# hermes_v2.net
KiCad netlist of a schematic drawn in EAGLE
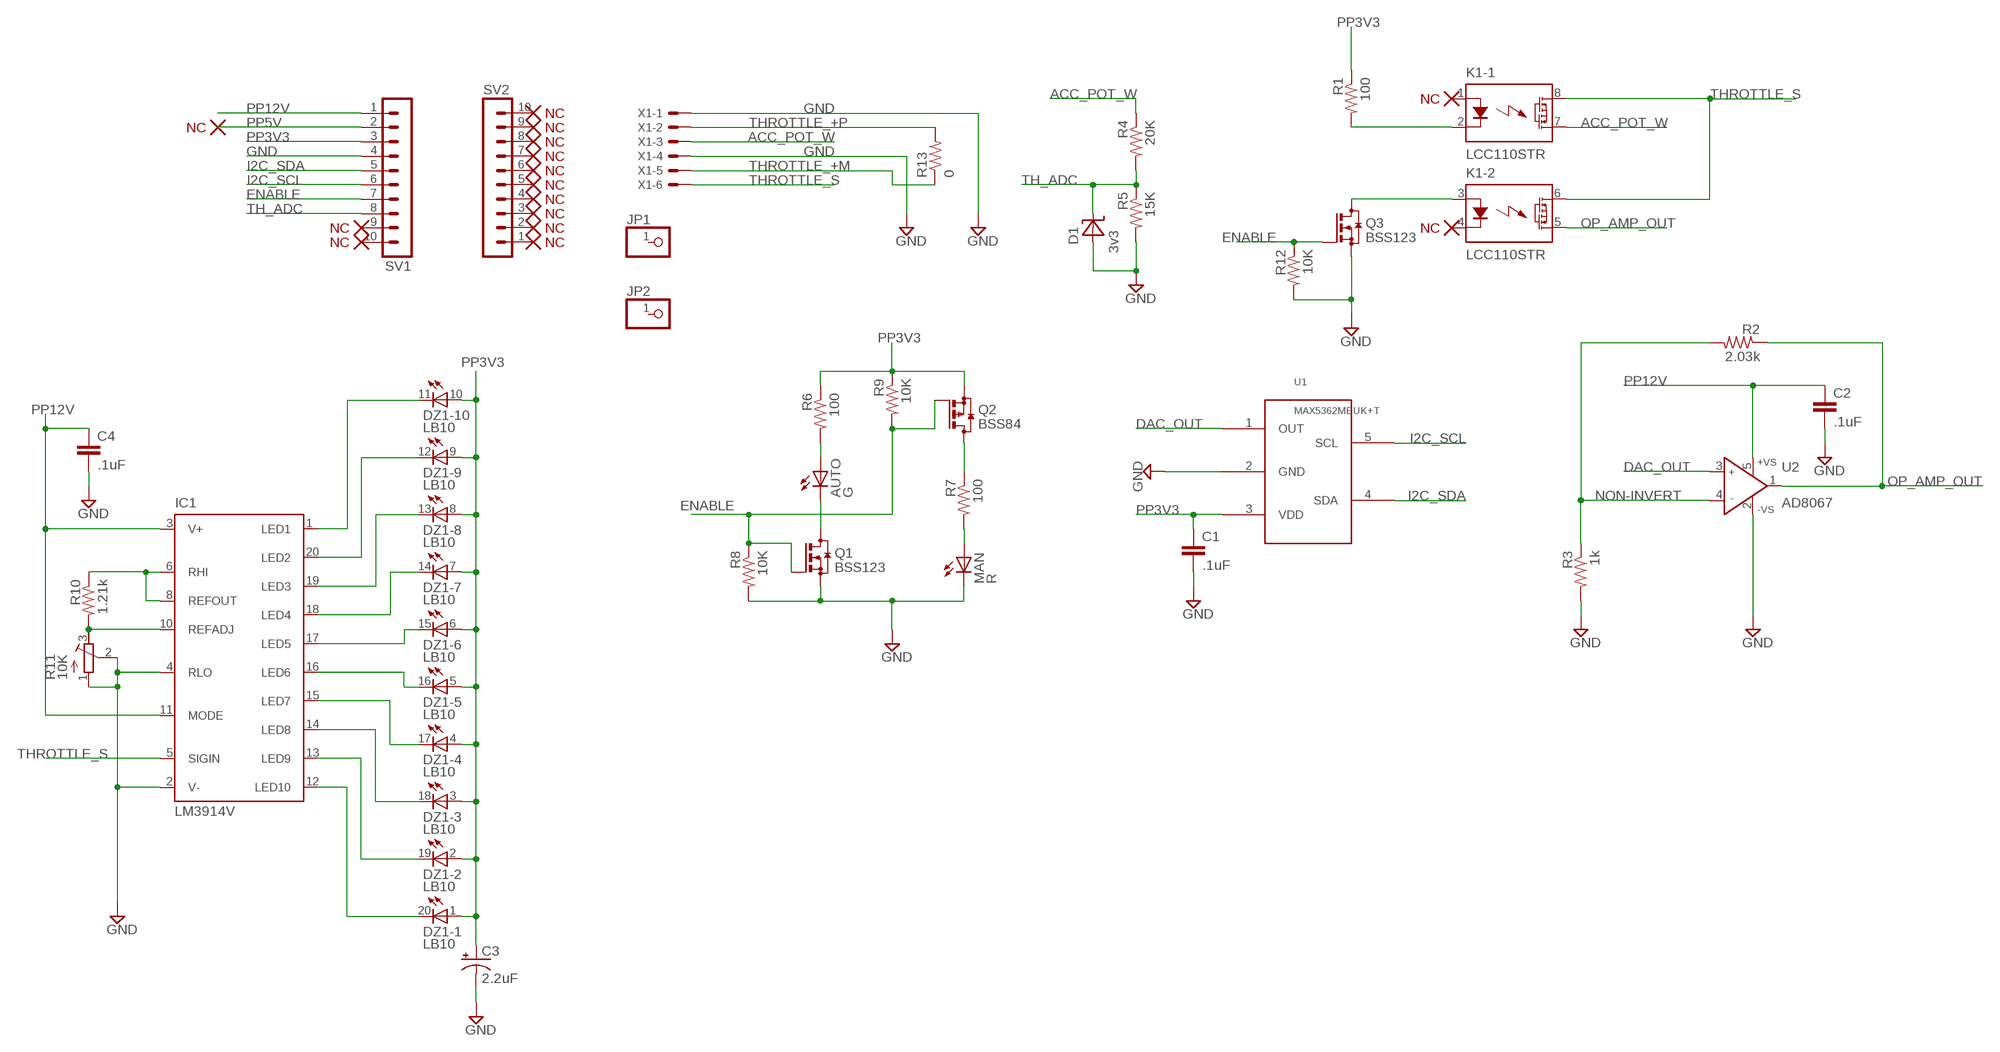
[diagram p0: schematic, sheet 1]

(export (version "E")
  (design (tool "Eeschema 10.0.6"))
  (components
    (comp (ref "AUTO")
      (value "G")
      (footprint "eagle-import:LED_SML0603")
      (libsource (lib "eagle-import") (part "LED_ESML0603"))
    )
    (comp (ref "C1")
      (value ".1uF")
      (footprint "eagle-import:C0402")
      (libsource (lib "eagle-import") (part "CC0402"))
    )
    (comp (ref "C2")
      (value ".1uF")
      (footprint "eagle-import:C0402")
      (libsource (lib "eagle-import") (part "CC0402"))
    )
    (comp (ref "C3")
      (value "2.2uF")
      (footprint "eagle-import:SMC_A")
      (libsource (lib "eagle-import") (part "CPOL-USSMCA"))
    )
    (comp (ref "C4")
      (value ".1uF")
      (footprint "eagle-import:C0402")
      (libsource (lib "eagle-import") (part "CC0402"))
    )
    (comp (ref "D1")
      (value "3v3")
      (footprint "eagle-import:SOD323_ST")
      (libsource (lib "eagle-import") (part "ZENER"))
    )
    (comp (ref "DZ1")
      (value "LB10")
      (footprint "eagle-import:LB10")
      (libsource (lib "eagle-import") (part "LB10"))
    )
    (comp (ref "IC1")
      (value "LM3914V")
      (footprint "eagle-import:PLCC20S")
      (libsource (lib "eagle-import") (part "LM391V4"))
    )
    (comp (ref "JP1")
      (value "PINHD-1X1")
      (footprint "eagle-import:1X01")
      (libsource (lib "eagle-import") (part "PINHD-1X1"))
    )
    (comp (ref "JP2")
      (value "PINHD-1X1")
      (footprint "eagle-import:1X01")
      (libsource (lib "eagle-import") (part "PINHD-1X1"))
    )
    (comp (ref "K1")
      (value "LCC110STR")
      (footprint "eagle-import:DIL08SMD")
      (fields (field (name "MF") "AROMAT/ MATSUSHITA") (field (name "MPN") "AQW654"))
      (libsource (lib "eagle-import") (part "AQWSMD654"))
    )
    (comp (ref "MAN")
      (value "R")
      (footprint "eagle-import:LED_SML0603")
      (libsource (lib "eagle-import") (part "LED_ESML0603"))
    )
    (comp (ref "Q1")
      (value "BSS123")
      (footprint "eagle-import:SOT23")
      (libsource (lib "eagle-import") (part "BSS123"))
    )
    (comp (ref "Q2")
      (value "BSS84")
      (footprint "eagle-import:SOT23")
      (libsource (lib "eagle-import") (part "BSS84"))
    )
    (comp (ref "Q3")
      (value "BSS123")
      (footprint "eagle-import:SOT23")
      (libsource (lib "eagle-import") (part "BSS123"))
    )
    (comp (ref "R1")
      (value "100")
      (footprint "eagle-import:R0603")
      (libsource (lib "eagle-import") (part "resistor_R-US_R0603"))
    )
    (comp (ref "R2")
      (value "2.03k")
      (footprint "eagle-import:R0603")
      (libsource (lib "eagle-import") (part "resistor_R-US_R0603"))
    )
    (comp (ref "R3")
      (value "1k")
      (footprint "eagle-import:R0603")
      (libsource (lib "eagle-import") (part "resistor_R-US_R0603"))
    )
    (comp (ref "R4")
      (value "20K")
      (footprint "eagle-import:R0603")
      (libsource (lib "eagle-import") (part "resistor_R-US_R0603"))
    )
    (comp (ref "R5")
      (value "15K")
      (footprint "eagle-import:R0603")
      (libsource (lib "eagle-import") (part "resistor_R-US_R0603"))
    )
    (comp (ref "R6")
      (value "100")
      (footprint "eagle-import:R0603")
      (libsource (lib "eagle-import") (part "resistor_R-US_R0603"))
    )
    (comp (ref "R7")
      (value "100")
      (footprint "eagle-import:R0603")
      (libsource (lib "eagle-import") (part "resistor_R-US_R0603"))
    )
    (comp (ref "R8")
      (value "10K")
      (footprint "eagle-import:R0603")
      (libsource (lib "eagle-import") (part "resistor_R-US_R0603"))
    )
    (comp (ref "R9")
      (value "10K")
      (footprint "eagle-import:R0603")
      (libsource (lib "eagle-import") (part "resistor_R-US_R0603"))
    )
    (comp (ref "R10")
      (value "1.21k")
      (footprint "eagle-import:R0603")
      (libsource (lib "eagle-import") (part "resistor_R-US_R0603"))
    )
    (comp (ref "R11")
      (value "10K")
      (footprint "eagle-import:RTRIM5X")
      (libsource (lib "eagle-import") (part "R-TRIMM5X"))
    )
    (comp (ref "R12")
      (value "10K")
      (footprint "eagle-import:R0603")
      (libsource (lib "eagle-import") (part "resistor_R-US_R0603"))
    )
    (comp (ref "R13")
      (value "0")
      (footprint "eagle-import:R0402")
      (libsource (lib "eagle-import") (part "R-US_R0402"))
    )
    (comp (ref "SV1")
      (value "MA10-1")
      (footprint "eagle-import:MA10-1")
      (libsource (lib "eagle-import") (part "MA10-1"))
    )
    (comp (ref "SV2")
      (value "MA10-1")
      (footprint "eagle-import:MA10-1")
      (libsource (lib "eagle-import") (part "MA10-1"))
    )
    (comp (ref "U1")
      (value "DAC")
      (footprint "eagle-import:SOT23-5")
      (libsource (lib "eagle-import") (part "DAC"))
    )
    (comp (ref "U2")
      (value "AD8067")
      (footprint "eagle-import:SOT23-5")
      (fields (field (name "MF") "ALTERA CORPORATION") (field (name "MPN") "AD8067ARTZ-REEL7"))
      (libsource (lib "eagle-import") (part "AD8067"))
    )
    (comp (ref "X1")
      (value "22-23-2061")
      (footprint "eagle-import:22-23-2061")
      (fields (field (name "MF") "MOLEX"))
      (libsource (lib "eagle-import") (part "22-23-2061"))
    )
  )
  (nets
    (net (code "1") (name "/ACC_POT_W") (class "Default")
      (node (ref "K1") (pin "7") (pinfunction "D2_7") (pintype "passive"))
      (node (ref "R4") (pin "1") (pinfunction "1_1") (pintype "passive"))
      (node (ref "X1") (pin "3") (pinfunction "S_3") (pintype "passive"))
    )
    (net (code "2") (name "/DAC_OUT") (class "Default")
      (node (ref "U1") (pin "1") (pinfunction "OUT_1") (pintype "bidirectional"))
      (node (ref "U2") (pin "3") (pinfunction "IN+_3") (pintype "input"))
    )
    (net (code "3") (name "/ENABLE") (class "Default")
      (node (ref "Q1") (pin "1") (pinfunction "G_1") (pintype "passive"))
      (node (ref "Q2") (pin "1") (pinfunction "G_1") (pintype "passive"))
      (node (ref "Q3") (pin "1") (pinfunction "G_1") (pintype "passive"))
      (node (ref "R12") (pin "1") (pinfunction "1_1") (pintype "passive"))
      (node (ref "R8") (pin "1") (pinfunction "1_1") (pintype "passive"))
      (node (ref "R9") (pin "2") (pinfunction "2_2") (pintype "passive"))
      (node (ref "SV1") (pin "7") (pinfunction "7_7") (pintype "passive"))
    )
    (net (code "4") (name "/I2C_SCL") (class "Default")
      (node (ref "SV1") (pin "6") (pinfunction "6_6") (pintype "passive"))
      (node (ref "U1") (pin "5") (pinfunction "SCL_5") (pintype "bidirectional"))
    )
    (net (code "5") (name "/I2C_SDA") (class "Default")
      (node (ref "SV1") (pin "5") (pinfunction "5_5") (pintype "passive"))
      (node (ref "U1") (pin "4") (pinfunction "SDA_4") (pintype "bidirectional"))
    )
    (net (code "6") (name "/NON-INVERT") (class "Default")
      (node (ref "R2") (pin "2") (pinfunction "2_2") (pintype "passive"))
      (node (ref "R3") (pin "1") (pinfunction "1_1") (pintype "passive"))
      (node (ref "U2") (pin "4") (pinfunction "IN-_4") (pintype "input"))
    )
    (net (code "7") (name "/OP_AMP_OUT") (class "Default")
      (node (ref "K1") (pin "5") (pinfunction "D2_5") (pintype "passive"))
      (node (ref "R2") (pin "1") (pinfunction "1_1") (pintype "passive"))
      (node (ref "U2") (pin "1") (pinfunction "OUT_1") (pintype "output"))
    )
    (net (code "8") (name "/PP3V3") (class "Default")
      (node (ref "C1") (pin "1") (pinfunction "1_1") (pintype "passive"))
      (node (ref "C3") (pin "+") (pinfunction "+_+") (pintype "passive"))
      (node (ref "DZ1") (pin "1") (pinfunction "A_1") (pintype "passive"))
      (node (ref "DZ1") (pin "10") (pinfunction "A_10") (pintype "passive"))
      (node (ref "DZ1") (pin "2") (pinfunction "A_2") (pintype "passive"))
      (node (ref "DZ1") (pin "3") (pinfunction "A_3") (pintype "passive"))
      (node (ref "DZ1") (pin "4") (pinfunction "A_4") (pintype "passive"))
      (node (ref "DZ1") (pin "5") (pinfunction "A_5") (pintype "passive"))
      (node (ref "DZ1") (pin "6") (pinfunction "A_6") (pintype "passive"))
      (node (ref "DZ1") (pin "7") (pinfunction "A_7") (pintype "passive"))
      (node (ref "DZ1") (pin "8") (pinfunction "A_8") (pintype "passive"))
      (node (ref "DZ1") (pin "9") (pinfunction "A_9") (pintype "passive"))
      (node (ref "Q2") (pin "2") (pinfunction "S_2") (pintype "passive"))
      (node (ref "R1") (pin "1") (pinfunction "1_1") (pintype "passive"))
      (node (ref "R6") (pin "1") (pinfunction "1_1") (pintype "passive"))
      (node (ref "R9") (pin "1") (pinfunction "1_1") (pintype "passive"))
      (node (ref "SV1") (pin "3") (pinfunction "3_3") (pintype "passive"))
      (node (ref "U1") (pin "3") (pinfunction "VDD_3") (pintype "bidirectional"))
    )
    (net (code "9") (name "/PP5V") (class "Default")
      (node (ref "SV1") (pin "2") (pinfunction "2_2") (pintype "passive"))
    )
    (net (code "10") (name "/PP12V") (class "Default")
      (node (ref "C2") (pin "1") (pinfunction "1_1") (pintype "passive"))
      (node (ref "C4") (pin "1") (pinfunction "1_1") (pintype "passive"))
      (node (ref "IC1") (pin "11") (pinfunction "MODE_11") (pintype "input"))
      (node (ref "IC1") (pin "3") (pinfunction "V+_3") (pintype "power_in"))
      (node (ref "SV1") (pin "1") (pinfunction "1_1") (pintype "passive"))
      (node (ref "U2") (pin "5") (pinfunction "+VS_5") (pintype "input"))
    )
    (net (code "11") (name "/THROTTLE_+M") (class "Default")
      (node (ref "R13") (pin "1") (pinfunction "1_1") (pintype "passive"))
      (node (ref "X1") (pin "5") (pinfunction "S_5") (pintype "passive"))
    )
    (net (code "12") (name "/THROTTLE_+P") (class "Default")
      (node (ref "R13") (pin "2") (pinfunction "2_2") (pintype "passive"))
      (node (ref "X1") (pin "2") (pinfunction "S_2") (pintype "passive"))
    )
    (net (code "13") (name "/THROTTLE_S") (class "Default")
      (node (ref "IC1") (pin "5") (pinfunction "SIGIN_5") (pintype "input"))
      (node (ref "K1") (pin "6") (pinfunction "D1_6") (pintype "passive"))
      (node (ref "K1") (pin "8") (pinfunction "D1_8") (pintype "passive"))
      (node (ref "X1") (pin "6") (pinfunction "S_6") (pintype "passive"))
    )
    (net (code "14") (name "/TH_ADC") (class "Default")
      (node (ref "D1") (pin "C") (pinfunction "C_C") (pintype "passive"))
      (node (ref "R4") (pin "2") (pinfunction "2_2") (pintype "passive"))
      (node (ref "R5") (pin "1") (pinfunction "1_1") (pintype "passive"))
      (node (ref "SV1") (pin "8") (pinfunction "8_8") (pintype "passive"))
    )
    (net (code "15") (name "GND") (class "Default")
      (node (ref "C1") (pin "2") (pinfunction "2_2") (pintype "passive"))
      (node (ref "C2") (pin "2") (pinfunction "2_2") (pintype "passive"))
      (node (ref "C3") (pin "-") (pinfunction "-_-") (pintype "passive"))
      (node (ref "C4") (pin "2") (pinfunction "2_2") (pintype "passive"))
      (node (ref "D1") (pin "A") (pinfunction "A_A") (pintype "passive"))
      (node (ref "IC1") (pin "2") (pinfunction "V-_2") (pintype "power_in"))
      (node (ref "IC1") (pin "4") (pinfunction "RLO_4") (pintype "input"))
      (node (ref "MAN") (pin "C") (pinfunction "C_C") (pintype "passive"))
      (node (ref "Q1") (pin "2") (pinfunction "S_2") (pintype "passive"))
      (node (ref "Q3") (pin "2") (pinfunction "S_2") (pintype "passive"))
      (node (ref "R11") (pin "1") (pinfunction "A_1") (pintype "passive"))
      (node (ref "R11") (pin "2") (pinfunction "S_2") (pintype "passive"))
      (node (ref "R12") (pin "2") (pinfunction "2_2") (pintype "passive"))
      (node (ref "R3") (pin "2") (pinfunction "2_2") (pintype "passive"))
      (node (ref "R5") (pin "2") (pinfunction "2_2") (pintype "passive"))
      (node (ref "R8") (pin "2") (pinfunction "2_2") (pintype "passive"))
      (node (ref "SV1") (pin "4") (pinfunction "4_4") (pintype "passive"))
      (node (ref "U1") (pin "2") (pinfunction "GND_2") (pintype "bidirectional"))
      (node (ref "U2") (pin "2") (pinfunction "-VS_2") (pintype "input"))
      (node (ref "X1") (pin "1") (pinfunction "S_1") (pintype "passive"))
      (node (ref "X1") (pin "4") (pinfunction "S_4") (pintype "passive"))
    )
    (net (code "16") (name "Net-(AUTO-PadA)") (class "Default")
      (node (ref "AUTO") (pin "A") (pinfunction "A_A") (pintype "passive"))
      (node (ref "R6") (pin "2") (pinfunction "2_2") (pintype "passive"))
    )
    (net (code "17") (name "Net-(DZ1A-C)") (class "Default")
      (node (ref "DZ1") (pin "20") (pinfunction "C_20") (pintype "passive"))
      (node (ref "IC1") (pin "12") (pinfunction "LED10_12") (pintype "output"))
    )
    (net (code "18") (name "Net-(DZ1B-C)") (class "Default")
      (node (ref "DZ1") (pin "11") (pinfunction "C_11") (pintype "passive"))
      (node (ref "IC1") (pin "1") (pinfunction "LED1_1") (pintype "output"))
    )
    (net (code "19") (name "Net-(DZ1C-C)") (class "Default")
      (node (ref "DZ1") (pin "19") (pinfunction "C_19") (pintype "passive"))
      (node (ref "IC1") (pin "13") (pinfunction "LED9_13") (pintype "output"))
    )
    (net (code "20") (name "Net-(DZ1D-C)") (class "Default")
      (node (ref "DZ1") (pin "18") (pinfunction "C_18") (pintype "passive"))
      (node (ref "IC1") (pin "14") (pinfunction "LED8_14") (pintype "output"))
    )
    (net (code "21") (name "Net-(DZ1E-C)") (class "Default")
      (node (ref "DZ1") (pin "17") (pinfunction "C_17") (pintype "passive"))
      (node (ref "IC1") (pin "15") (pinfunction "LED7_15") (pintype "output"))
    )
    (net (code "22") (name "Net-(DZ1F-C)") (class "Default")
      (node (ref "DZ1") (pin "16") (pinfunction "C_16") (pintype "passive"))
      (node (ref "IC1") (pin "16") (pinfunction "LED6_16") (pintype "output"))
    )
    (net (code "23") (name "Net-(DZ1G-C)") (class "Default")
      (node (ref "DZ1") (pin "15") (pinfunction "C_15") (pintype "passive"))
      (node (ref "IC1") (pin "17") (pinfunction "LED5_17") (pintype "output"))
    )
    (net (code "24") (name "Net-(DZ1H-C)") (class "Default")
      (node (ref "DZ1") (pin "14") (pinfunction "C_14") (pintype "passive"))
      (node (ref "IC1") (pin "18") (pinfunction "LED4_18") (pintype "output"))
    )
    (net (code "25") (name "Net-(DZ1I-C)") (class "Default")
      (node (ref "DZ1") (pin "13") (pinfunction "C_13") (pintype "passive"))
      (node (ref "IC1") (pin "19") (pinfunction "LED3_19") (pintype "output"))
    )
    (net (code "26") (name "Net-(DZ1J-C)") (class "Default")
      (node (ref "DZ1") (pin "12") (pinfunction "C_12") (pintype "passive"))
      (node (ref "IC1") (pin "20") (pinfunction "LED2_20") (pintype "output"))
    )
    (net (code "27") (name "Net-(IC1-REFADJ)") (class "Default")
      (node (ref "IC1") (pin "10") (pinfunction "REFADJ_10") (pintype "passive"))
      (node (ref "R10") (pin "2") (pinfunction "2_2") (pintype "passive"))
      (node (ref "R11") (pin "3") (pinfunction "E_3") (pintype "passive"))
    )
    (net (code "28") (name "Net-(IC1-REFOUT)") (class "Default")
      (node (ref "IC1") (pin "6") (pinfunction "RHI_6") (pintype "input"))
      (node (ref "IC1") (pin "8") (pinfunction "REFOUT_8") (pintype "output"))
      (node (ref "R10") (pin "1") (pinfunction "1_1") (pintype "passive"))
    )
    (net (code "29") (name "Net-(K1A-K)") (class "Default")
      (node (ref "K1") (pin "2") (pinfunction "K_2") (pintype "passive"))
      (node (ref "R1") (pin "2") (pinfunction "2_2") (pintype "passive"))
    )
    (net (code "30") (name "Net-(K1B-A)") (class "Default")
      (node (ref "K1") (pin "3") (pinfunction "A_3") (pintype "passive"))
      (node (ref "Q3") (pin "3") (pinfunction "D_3") (pintype "passive"))
    )
    (net (code "31") (name "Net-(MAN-PadA)") (class "Default")
      (node (ref "MAN") (pin "A") (pinfunction "A_A") (pintype "passive"))
      (node (ref "R7") (pin "2") (pinfunction "2_2") (pintype "passive"))
    )
    (net (code "32") (name "Net-(Q1-D)") (class "Default")
      (node (ref "AUTO") (pin "C") (pinfunction "C_C") (pintype "passive"))
      (node (ref "Q1") (pin "3") (pinfunction "D_3") (pintype "passive"))
    )
    (net (code "33") (name "Net-(Q2-D)") (class "Default")
      (node (ref "Q2") (pin "3") (pinfunction "D_3") (pintype "passive"))
      (node (ref "R7") (pin "1") (pinfunction "1_1") (pintype "passive"))
    )
    (net (code "34") (name "unconnected-(JP1-Pad1)") (class "Default")
      (node (ref "JP1") (pin "1") (pinfunction "1_1") (pintype "passive"))
    )
    (net (code "35") (name "unconnected-(JP2-Pad1)") (class "Default")
      (node (ref "JP2") (pin "1") (pinfunction "1_1") (pintype "passive"))
    )
    (net (code "36") (name "unconnected-(K1A-A-Pad1)") (class "Default")
      (node (ref "K1") (pin "1") (pinfunction "A_1") (pintype "passive"))
    )
    (net (code "37") (name "unconnected-(K1B-K-Pad4)") (class "Default")
      (node (ref "K1") (pin "4") (pinfunction "K_4") (pintype "passive"))
    )
    (net (code "38") (name "unconnected-(SV1-Pad9)") (class "Default")
      (node (ref "SV1") (pin "9") (pinfunction "9_9") (pintype "passive"))
    )
    (net (code "39") (name "unconnected-(SV1-Pad10)") (class "Default")
      (node (ref "SV1") (pin "10") (pinfunction "10_10") (pintype "passive"))
    )
    (net (code "40") (name "unconnected-(SV2-Pad1)") (class "Default")
      (node (ref "SV2") (pin "1") (pinfunction "1_1") (pintype "passive"))
    )
    (net (code "41") (name "unconnected-(SV2-Pad2)") (class "Default")
      (node (ref "SV2") (pin "2") (pinfunction "2_2") (pintype "passive"))
    )
    (net (code "42") (name "unconnected-(SV2-Pad3)") (class "Default")
      (node (ref "SV2") (pin "3") (pinfunction "3_3") (pintype "passive"))
    )
    (net (code "43") (name "unconnected-(SV2-Pad4)") (class "Default")
      (node (ref "SV2") (pin "4") (pinfunction "4_4") (pintype "passive"))
    )
    (net (code "44") (name "unconnected-(SV2-Pad5)") (class "Default")
      (node (ref "SV2") (pin "5") (pinfunction "5_5") (pintype "passive"))
    )
    (net (code "45") (name "unconnected-(SV2-Pad6)") (class "Default")
      (node (ref "SV2") (pin "6") (pinfunction "6_6") (pintype "passive"))
    )
    (net (code "46") (name "unconnected-(SV2-Pad7)") (class "Default")
      (node (ref "SV2") (pin "7") (pinfunction "7_7") (pintype "passive"))
    )
    (net (code "47") (name "unconnected-(SV2-Pad8)") (class "Default")
      (node (ref "SV2") (pin "8") (pinfunction "8_8") (pintype "passive"))
    )
    (net (code "48") (name "unconnected-(SV2-Pad9)") (class "Default")
      (node (ref "SV2") (pin "9") (pinfunction "9_9") (pintype "passive"))
    )
    (net (code "49") (name "unconnected-(SV2-Pad10)") (class "Default")
      (node (ref "SV2") (pin "10") (pinfunction "10_10") (pintype "passive"))
    )
  )
)
